# STM32F446RE_BES.net
KiCad netlist of a schematic drawn in Altium Designer
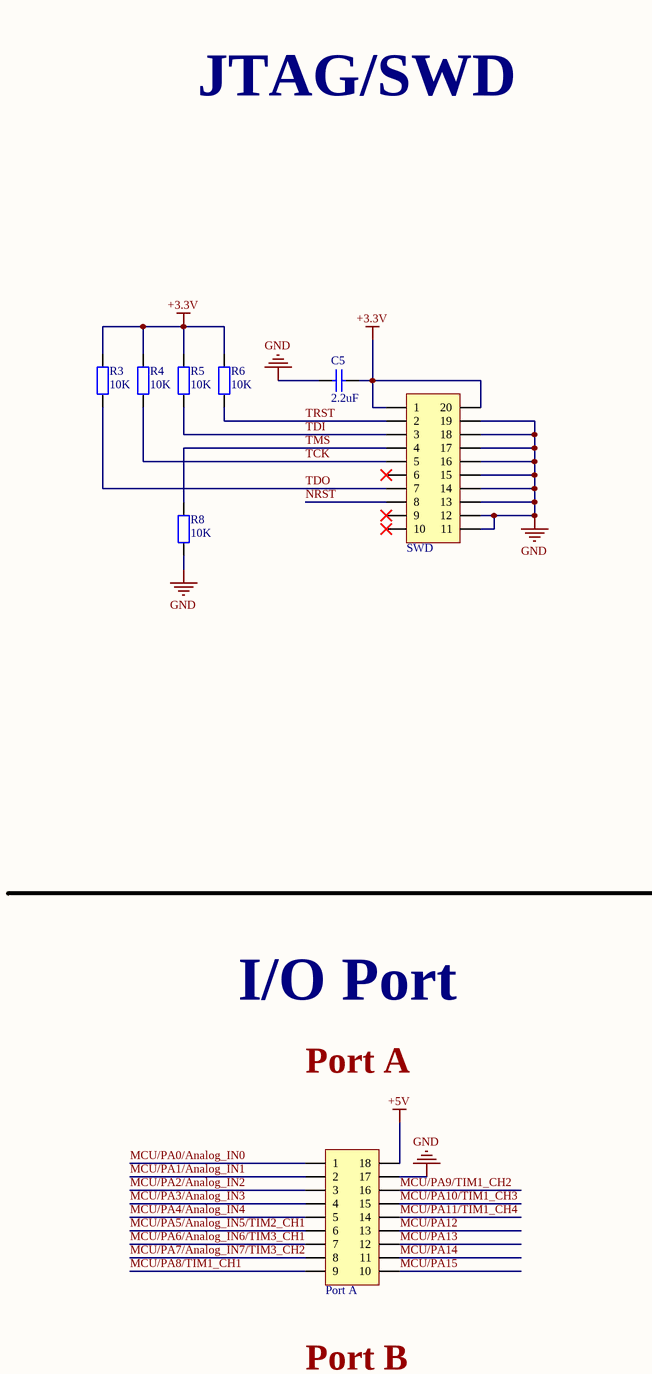
[diagram p0: STM32F446RE_BES.SchDoc, top left]
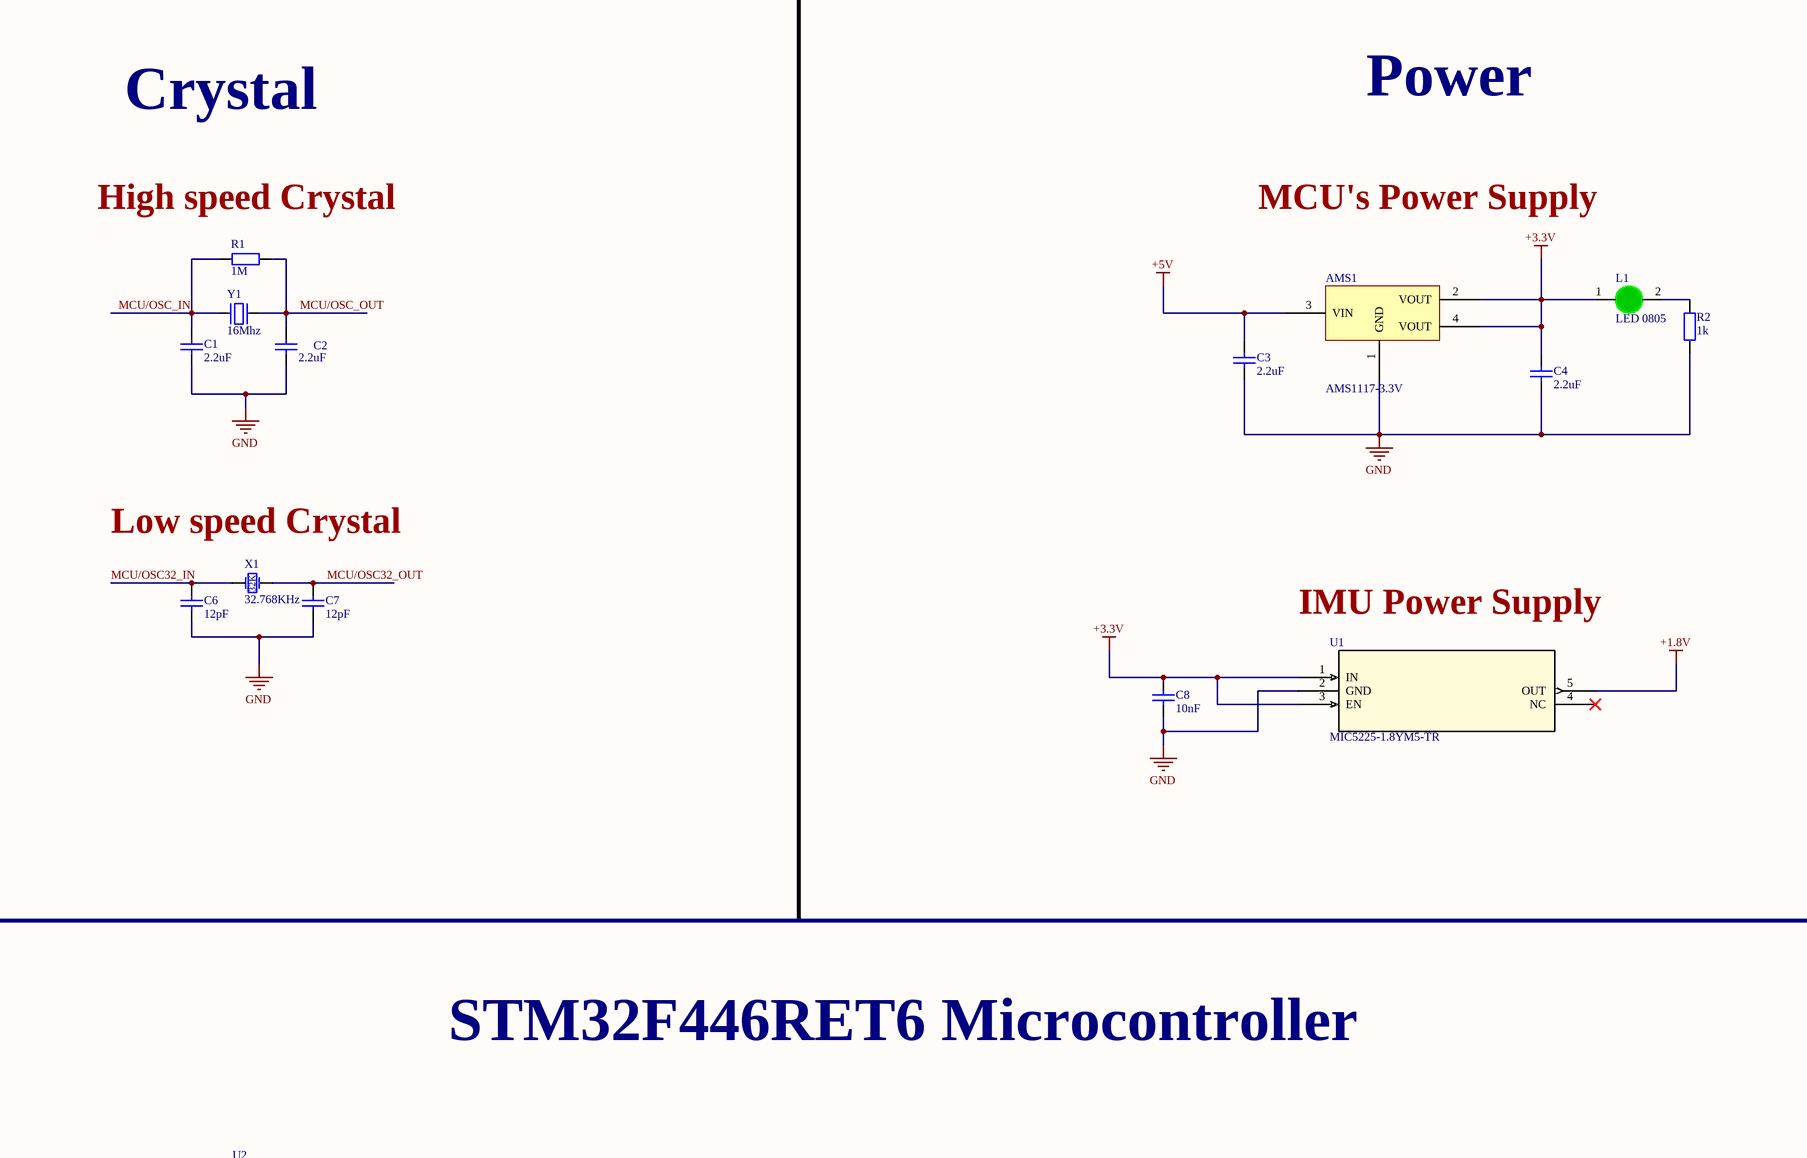
[diagram p1: STM32F446RE_BES.SchDoc, top middle]
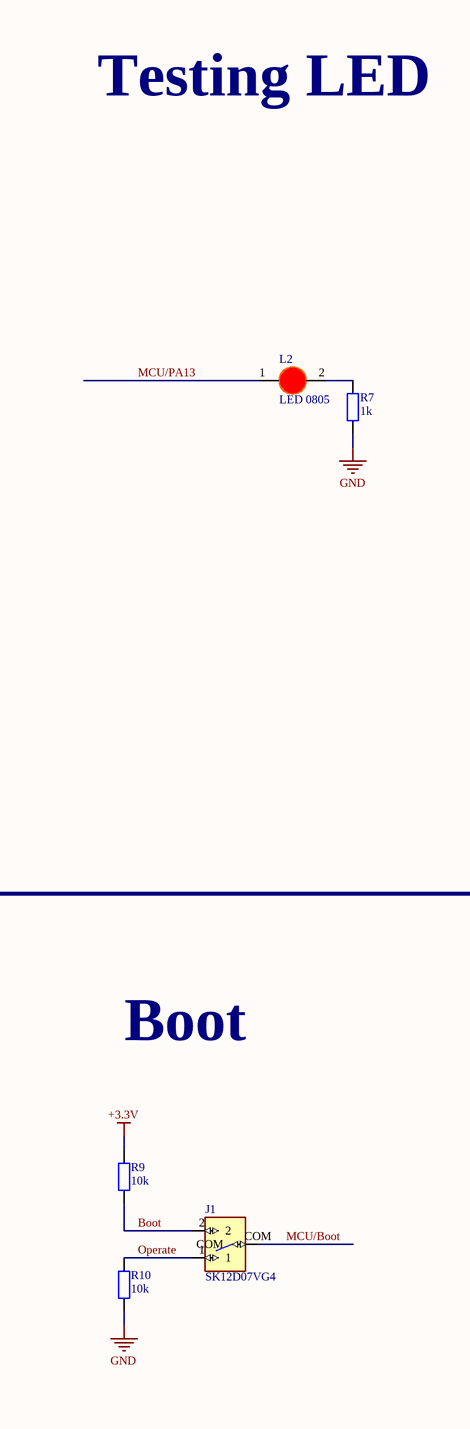
[diagram p2: STM32F446RE_BES.SchDoc, top right]
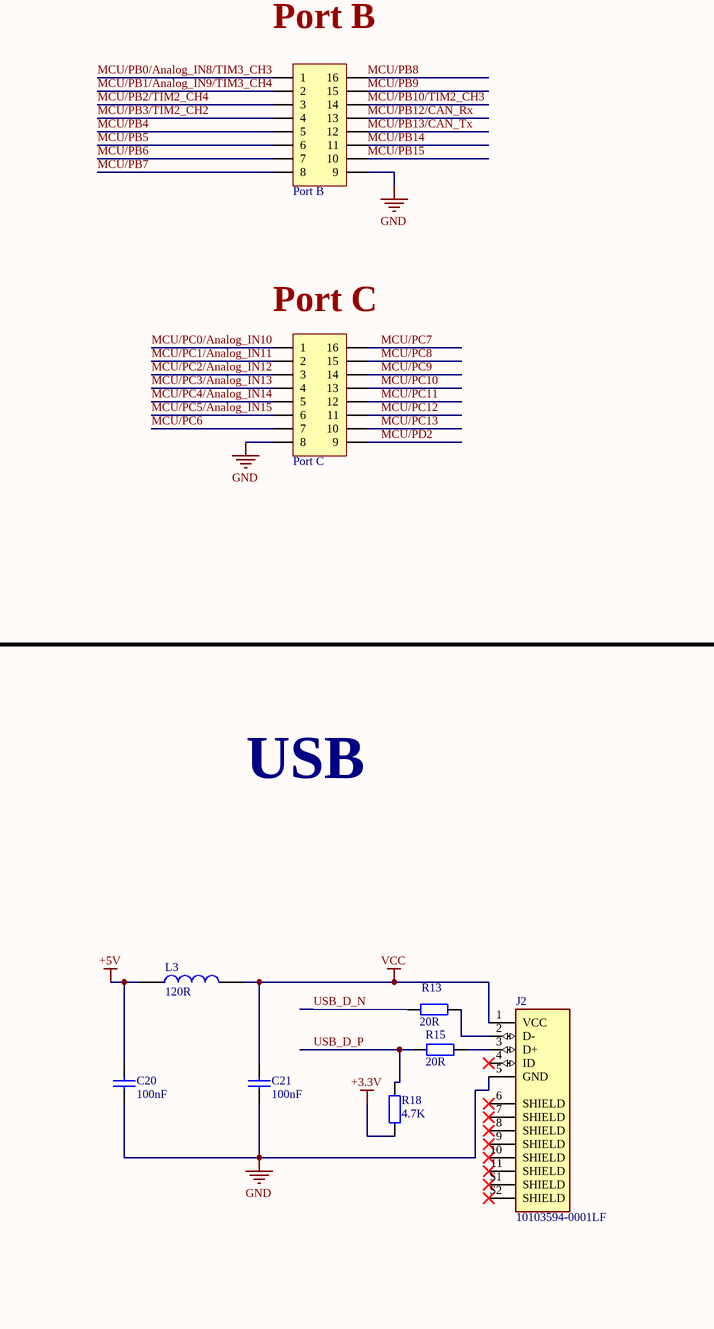
[diagram p3: STM32F446RE_BES.SchDoc, bottom left]
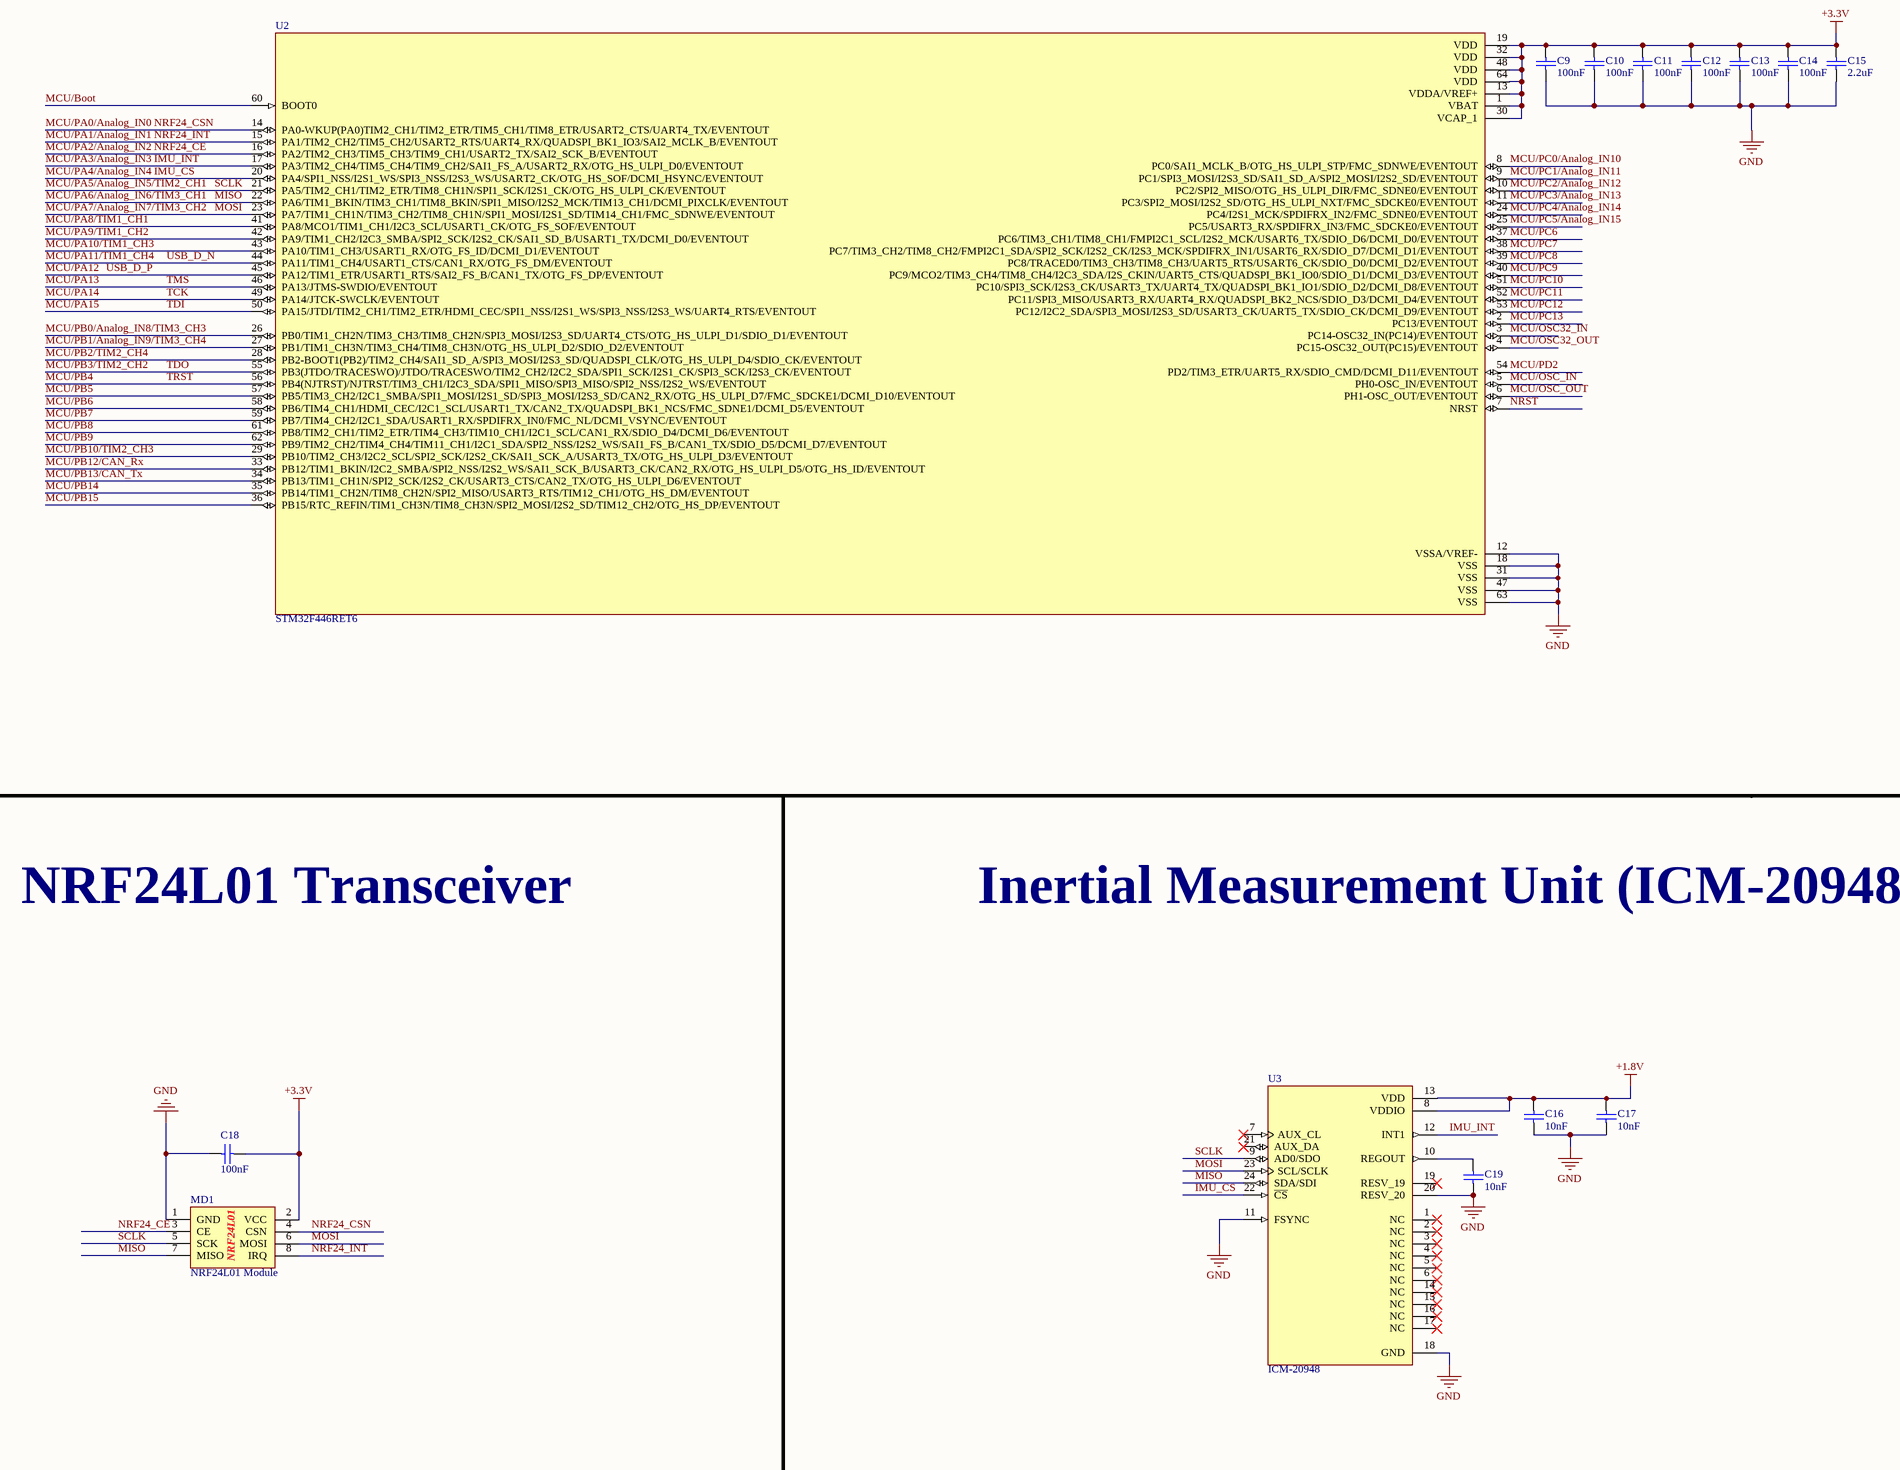
[diagram p4: STM32F446RE_BES.SchDoc, bottom middle]
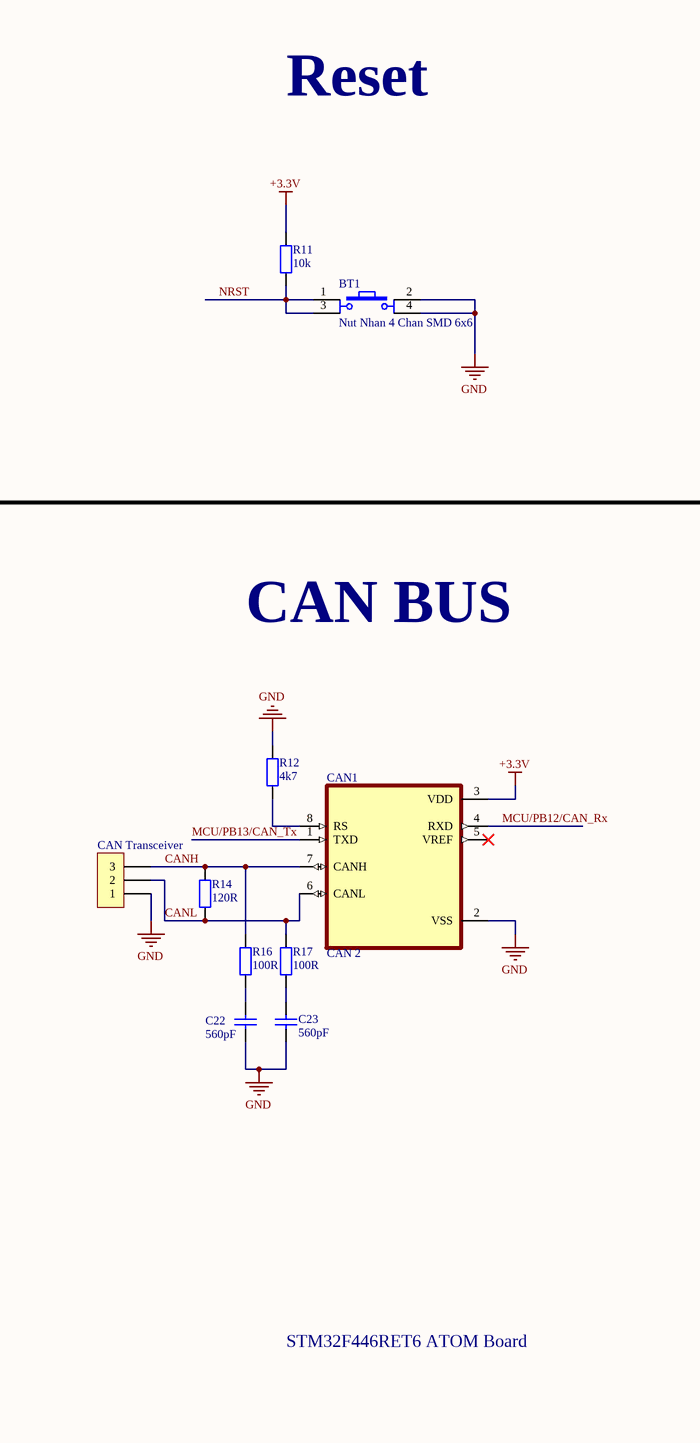
[diagram p5: STM32F446RE_BES.SchDoc, bottom right]

(export (version "E")
  (design (tool "Eeschema 10.0.6"))
  (components
    (comp (ref "AMS1")
      (value "AMS1117-3.3V")
      (footprint "SOT223")
      (description "Dán")
      (libsource (lib "Altium_Lib_by_KhueNguyenCreator") (part "AMS1117 SMD"))
    )
    (comp (ref "BT1")
      (value "Nut Nhan 4 Chan SMD 6x6")
      (footprint "Nut Nhan 4 Chan SMD 6x6")
      (description "Nut Nhan 4 Chan 6.2x6.2x3.5")
      (libsource (lib "Altium_Lib_by_KhueNguyenCreator") (part "Nut Nhan 4 Chan SMD 6x6"))
    )
    (comp (ref "C1")
      (value "2.2uF")
      (footprint "tu 0805")
      (description "Dán")
      (libsource (lib "Altium_Lib_by_KhueNguyenCreator") (part "Tu 0805 10pF 50V 10%"))
    )
    (comp (ref "C2")
      (value "2.2uF")
      (footprint "tu 0805")
      (description "Dán")
      (libsource (lib "Altium_Lib_by_KhueNguyenCreator") (part "Tu 0805 10pF 50V 10%"))
    )
    (comp (ref "C3")
      (value "2.2uF")
      (footprint "tu 0805")
      (description "Dán")
      (libsource (lib "Altium_Lib_by_KhueNguyenCreator") (part "Tu 0805 10pF 50V 10%"))
    )
    (comp (ref "C4")
      (value "2.2uF")
      (footprint "tu 0805")
      (description "Dán")
      (libsource (lib "Altium_Lib_by_KhueNguyenCreator") (part "Tu 0805 10pF 50V 10%"))
    )
    (comp (ref "C5")
      (value "2.2uF")
      (footprint "tu 0805")
      (description "Dán")
      (libsource (lib "Altium_Lib_by_KhueNguyenCreator") (part "Tu 0805 10pF 50V 10%"))
    )
    (comp (ref "C6")
      (value "12pF")
      (footprint "tu 0805")
      (description "Dán")
      (libsource (lib "Altium_Lib_by_KhueNguyenCreator") (part "Tu 0805 10pF 50V 10%"))
    )
    (comp (ref "C7")
      (value "12pF")
      (footprint "tu 0805")
      (description "Dán")
      (libsource (lib "Altium_Lib_by_KhueNguyenCreator") (part "Tu 0805 10pF 50V 10%"))
    )
    (comp (ref "C8")
      (value "10nF")
      (footprint "tu 0805")
      (description "Dán")
      (libsource (lib "Altium_Lib_by_KhueNguyenCreator") (part "Tu 0805 106 16V 10%"))
    )
    (comp (ref "C9")
      (value "100nF")
      (footprint "tu 0805")
      (description "Dán")
      (libsource (lib "Altium_Lib_by_KhueNguyenCreator") (part "Tu 0805 10pF 50V 10%"))
    )
    (comp (ref "C10")
      (value "100nF")
      (footprint "tu 0805")
      (description "Dán")
      (libsource (lib "Altium_Lib_by_KhueNguyenCreator") (part "Tu 0805 10pF 50V 10%"))
    )
    (comp (ref "C11")
      (value "100nF")
      (footprint "tu 0805")
      (description "Dán")
      (libsource (lib "Altium_Lib_by_KhueNguyenCreator") (part "Tu 0805 10pF 50V 10%"))
    )
    (comp (ref "C12")
      (value "100nF")
      (footprint "tu 0805")
      (description "Dán")
      (libsource (lib "Altium_Lib_by_KhueNguyenCreator") (part "Tu 0805 10pF 50V 10%"))
    )
    (comp (ref "C13")
      (value "100nF")
      (footprint "tu 0805")
      (description "Dán")
      (libsource (lib "Altium_Lib_by_KhueNguyenCreator") (part "Tu 0805 10pF 50V 10%"))
    )
    (comp (ref "C14")
      (value "100nF")
      (footprint "tu 0805")
      (description "Dán")
      (libsource (lib "Altium_Lib_by_KhueNguyenCreator") (part "Tu 0805 10pF 50V 10%"))
    )
    (comp (ref "C15")
      (value "2.2uF")
      (footprint "tu 0805")
      (description "Dán")
      (libsource (lib "Altium_Lib_by_KhueNguyenCreator") (part "Tu 0805 10pF 50V 10%"))
    )
    (comp (ref "C16")
      (value "10nF")
      (footprint "tu 0805")
      (description "Dán")
      (libsource (lib "Altium_Lib_by_KhueNguyenCreator") (part "Tu 0805 106 16V 10%"))
    )
    (comp (ref "C17")
      (value "10nF")
      (footprint "tu 0805")
      (description "Dán")
      (libsource (lib "Altium_Lib_by_KhueNguyenCreator") (part "Tu 0805 106 16V 10%"))
    )
    (comp (ref "C18")
      (value "100nF")
      (footprint "tu 0805")
      (description "Dán")
      (libsource (lib "Altium_Lib_by_KhueNguyenCreator") (part "Tu 0805 106 16V 10%"))
    )
    (comp (ref "C19")
      (value "10nF")
      (footprint "tu 0805")
      (description "Dán")
      (libsource (lib "Altium_Lib_by_KhueNguyenCreator") (part "Tu 0805 106 16V 10%"))
    )
    (comp (ref "C20")
      (value "100nF")
      (footprint "tu 0805")
      (description "Dán")
      (libsource (lib "Altium_Lib_by_KhueNguyenCreator") (part "Tu 0805 106 16V 10%"))
    )
    (comp (ref "C21")
      (value "100nF")
      (footprint "tu 0805")
      (description "Dán")
      (libsource (lib "Altium_Lib_by_KhueNguyenCreator") (part "Tu 0805 106 16V 10%"))
    )
    (comp (ref "C22")
      (value "560pF")
      (footprint "tu 0805")
      (description "Dán")
      (libsource (lib "Altium_Lib_by_KhueNguyenCreator") (part "Tu 0805 106 16V 10%"))
    )
    (comp (ref "C23")
      (value "560pF")
      (footprint "tu 0805")
      (description "Dán")
      (libsource (lib "Altium_Lib_by_KhueNguyenCreator") (part "Tu 0805 106 16V 10%"))
    )
    (comp (ref "CAN 1")
      (value "CAN Transceiver")
      (footprint "XH2.54M-3")
      (description "Cắm")
      (libsource (lib "Altium_Lib_by_KhueNguyenCreator") (part "Header 3P 2.54 Duc Thang"))
    )
    (comp (ref "CAN1")
      (value "CAN 2")
      (footprint "MCP2551-I_SN:SOIC127P599X175-8N")
      (fields
        (field (name "MF") "{'manufacturer': u'Microchip Technology'}")
        (field (name "MP") "MCP2551-I/SN")
      )
      (libsource (lib "*") (part "MCP2551-I/SN"))
    )
    (comp (ref "J1")
      (value "SK12D07VG4")
      (footprint "SK12D07VG4")
      (description "Switch Slide ON ON SPDT Side Slide 0.3A 30VDC PC Pins Bracket Mount/Through Hole Bulk")
      (fields (field (name "MF") "C&K"))
      (libsource (lib "SK12D07VG4") (part "SK12D07VG4"))
    )
    (comp (ref "J2")
      (value "10103594-0001LF")
      (footprint "10103594-0001LF:AMPHENOL_10103594-0001LF")
      (description "USB - micro B USB 2.0 Receptacle Connector 5 Position Surface Mount, Right Angle; Through Hole")
      (fields (field (name "MF") "{'manufacturer': u'FCI Connectors'}"))
      (libsource (lib "*") (part "10103594-0001LF"))
    )
    (comp (ref "L1")
      (value "LED 0805")
      (footprint "LED-0805-Green")
      (description "Dán")
      (libsource (lib "Altium_Lib_by_KhueNguyenCreator") (part "LED 0805 Xanh La"))
    )
    (comp (ref "L2")
      (value "LED 0805")
      (footprint "LED-0805-Red")
      (description "Dán")
      (libsource (lib "Altium_Lib_by_KhueNguyenCreator") (part "LED 0805 Do"))
    )
    (comp (ref "L3")
      (value "120R")
      (footprint "IND-0603 (1608)")
      (description "IND-FERRITE BEAD 23 OHM  4A 0603 1LN")
      (fields (field (name "MPN") "FBMJ1608HM230NT"))
      (libsource (lib "BYTECH_HW_LIB_2019 (1)") (part "FBMJ1608HM230NT"))
    )
    (comp (ref "MD1")
      (value "NRF24L01 Module")
      (footprint "NRF24L01")
      (libsource (lib "Altium_Lib_by_KhueNguyenCreator") (part "NRF24L01 Module"))
    )
    (comp (ref "Port A")
      (value "Port A")
      (footprint "JP 2x9 DT")
      (description "Cắm")
      (libsource (lib "Altium_Lib_by_KhueNguyenCreator") (part "JP 2x9 2.54 Duc Thang"))
    )
    (comp (ref "Port B")
      (value "Port B")
      (footprint "JP 2x8 DT")
      (description "Cắm")
      (libsource (lib "Altium_Lib_by_KhueNguyenCreator") (part "JP 2x8 2.54 Duc Thang"))
    )
    (comp (ref "Port C")
      (value "Port C")
      (footprint "JP 2x8 DT")
      (description "Cắm")
      (libsource (lib "Altium_Lib_by_KhueNguyenCreator") (part "JP 2x8 2.54 Duc Thang"))
    )
    (comp (ref "R1")
      (value "1M")
      (footprint "tro smd 0805")
      (description "Dán")
      (libsource (lib "Altium_Lib_by_KhueNguyenCreator") (part "Tro 0805 1% 1k"))
    )
    (comp (ref "R2")
      (value "1k")
      (footprint "tro smd 0805")
      (description "Dán")
      (libsource (lib "Altium_Lib_by_KhueNguyenCreator") (part "Tro 0805 1% 1k"))
    )
    (comp (ref "R3")
      (value "10K")
      (footprint "tro smd 0805")
      (description "Dán")
      (libsource (lib "Altium_Lib_by_KhueNguyenCreator") (part "Tro 0805 1% 10k"))
    )
    (comp (ref "R4")
      (value "10K")
      (footprint "tro smd 0805")
      (description "Dán")
      (libsource (lib "Altium_Lib_by_KhueNguyenCreator") (part "Tro 0805 1% 10k"))
    )
    (comp (ref "R5")
      (value "10K")
      (footprint "tro smd 0805")
      (description "Dán")
      (libsource (lib "Altium_Lib_by_KhueNguyenCreator") (part "Tro 0805 1% 10k"))
    )
    (comp (ref "R6")
      (value "10K")
      (footprint "tro smd 0805")
      (description "Dán")
      (libsource (lib "Altium_Lib_by_KhueNguyenCreator") (part "Tro 0805 1% 10k"))
    )
    (comp (ref "R7")
      (value "1k")
      (footprint "tro smd 0805")
      (description "Dán")
      (libsource (lib "Altium_Lib_by_KhueNguyenCreator") (part "Tro 0805 1% 1k"))
    )
    (comp (ref "R8")
      (value "10K")
      (footprint "tro smd 0805")
      (description "Dán")
      (libsource (lib "Altium_Lib_by_KhueNguyenCreator") (part "Tro 0805 1% 10k"))
    )
    (comp (ref "R9")
      (value "10k")
      (footprint "tro smd 0805")
      (description "Dán")
      (libsource (lib "Altium_Lib_by_KhueNguyenCreator") (part "Tro 0805 1% 1k"))
    )
    (comp (ref "R10")
      (value "10k")
      (footprint "tro smd 0805")
      (description "Dán")
      (libsource (lib "Altium_Lib_by_KhueNguyenCreator") (part "Tro 0805 1% 1k"))
    )
    (comp (ref "R11")
      (value "10k")
      (footprint "tro smd 0805")
      (description "Dán")
      (libsource (lib "Altium_Lib_by_KhueNguyenCreator") (part "Tro 0805 1% 1k"))
    )
    (comp (ref "R12")
      (value "4k7")
      (footprint "tro smd 0805")
      (description "Dán")
      (libsource (lib "Altium_Lib_by_KhueNguyenCreator") (part "Tro 0805 1% 10k"))
    )
    (comp (ref "R13")
      (value "20R")
      (footprint "tro smd 0805")
      (description "Dán")
      (libsource (lib "Altium_Lib_by_KhueNguyenCreator") (part "Tro 0805 1% 10k"))
    )
    (comp (ref "R14")
      (value "120R")
      (footprint "tro smd 0805")
      (description "Dán")
      (libsource (lib "Altium_Lib_by_KhueNguyenCreator") (part "Tro 0805 1% 10k"))
    )
    (comp (ref "R15")
      (value "20R")
      (footprint "tro smd 0805")
      (description "Dán")
      (libsource (lib "Altium_Lib_by_KhueNguyenCreator") (part "Tro 0805 1% 10k"))
    )
    (comp (ref "R16")
      (value "100R")
      (footprint "tro smd 0805")
      (description "Dán")
      (libsource (lib "Altium_Lib_by_KhueNguyenCreator") (part "Tro 0805 1% 10k"))
    )
    (comp (ref "R17")
      (value "100R")
      (footprint "tro smd 0805")
      (description "Dán")
      (libsource (lib "Altium_Lib_by_KhueNguyenCreator") (part "Tro 0805 1% 10k"))
    )
    (comp (ref "R18")
      (value "4.7K")
      (footprint "tro smd 0805")
      (description "Dán")
      (libsource (lib "Altium_Lib_by_KhueNguyenCreator") (part "Tro 0805 1% 10k"))
    )
    (comp (ref "SWD1")
      (value "SWD")
      (footprint "JP 2x10 DT")
      (description "Cắm")
      (libsource (lib "Altium_Lib_by_KhueNguyenCreator") (part "JP 2x10 2.54 Duc Thang"))
    )
    (comp (ref "U1")
      (value "MIC5225-1.8YM5-TR")
      (footprint "SOT-23-5_M5_MCH")
      (description "No Description Available")
      (libsource (lib "MIC5225-1P8YM5-TR") (part "MIC5225-1.8YM5-TR"))
    )
    (comp (ref "U2")
      (value "STM32F446RET6")
      (footprint "QFP50P1200X1200X160-64N")
      (description "MCU 32-Bit STM32 ARM Cortex M4 RISC 512KB Flash 2.5V/3.3V 64-Pin LQFP Tray")
      (fields (field (name "MF") "{'manufacturer': u'STMicroelectronics'}"))
      (libsource (lib "SnapEDA_Library") (part "STM32F446RET6"))
    )
    (comp (ref "U3")
      (value "ICM-20948")
      (footprint "QFN40P300X300X105-24N")
      (description "Accelerometer, Gyroscope, Magnetometer, 9 Axis Sensor IÂ²C, SPI Output")
      (libsource (lib "ICM-20948") (part "ICM-20948"))
    )
    (comp (ref "X1")
      (value "32.768KHz")
      (footprint "Crystal_ABS07_SMD-3.2x1.5MM")
      (description "CRYSTAL 32.7680KHZ 12.5pF SMD")
      (fields (field (name "MPN") "ABS07-32.768KHZ-T"))
      (libsource (lib "BYTECH_HW_LIB_2019 (1)") (part "ABS07-32.768KHZ-T"))
    )
    (comp (ref "Y1")
      (value "16Mhz")
      (footprint "Thach Anh 2 chan cam")
      (description "Crystal For all Crystal 2pin.")
      (libsource (lib "Altium_Lib_by_KhueNguyenCreator") (part "Thach Anh 2 chan Cam"))
    )
  )
  (nets
    (net (code "1") (name "+1.8V") (class "Default")
      (node (ref "C16") (pin "1") (pinfunction "1_1") (pintype "passive"))
      (node (ref "C17") (pin "1") (pinfunction "1_1") (pintype "passive"))
      (node (ref "U1") (pin "5") (pinfunction "OUT_5") (pintype "output"))
      (node (ref "U3") (pin "13") (pinfunction "VDD_13") (pintype "power_in"))
      (node (ref "U3") (pin "8") (pinfunction "VDDIO_8") (pintype "power_in"))
    )
    (net (code "2") (name "+3.3V") (class "Default")
      (node (ref "AMS1") (pin "2") (pinfunction "VOUT_2") (pintype "passive"))
      (node (ref "AMS1") (pin "4") (pinfunction "VOUT_4") (pintype "passive"))
      (node (ref "C10") (pin "1") (pinfunction "1_1") (pintype "passive"))
      (node (ref "C11") (pin "1") (pinfunction "1_1") (pintype "passive"))
      (node (ref "C12") (pin "1") (pinfunction "1_1") (pintype "passive"))
      (node (ref "C13") (pin "1") (pinfunction "1_1") (pintype "passive"))
      (node (ref "C14") (pin "1") (pinfunction "1_1") (pintype "passive"))
      (node (ref "C15") (pin "1") (pinfunction "1_1") (pintype "passive"))
      (node (ref "C18") (pin "1") (pinfunction "1_1") (pintype "passive"))
      (node (ref "C4") (pin "1") (pinfunction "1_1") (pintype "passive"))
      (node (ref "C5") (pin "2") (pinfunction "2_2") (pintype "passive"))
      (node (ref "C8") (pin "1") (pinfunction "1_1") (pintype "passive"))
      (node (ref "C9") (pin "1") (pinfunction "1_1") (pintype "passive"))
      (node (ref "CAN1") (pin "3") (pinfunction "VDD_3") (pintype "power_in"))
      (node (ref "L1") (pin "1") (pinfunction "A_1") (pintype "passive"))
      (node (ref "MD1") (pin "2") (pinfunction "VCC_2") (pintype "passive"))
      (node (ref "R11") (pin "1") (pinfunction "1_1") (pintype "passive"))
      (node (ref "R18") (pin "2") (pinfunction "2_2") (pintype "passive"))
      (node (ref "R3") (pin "2") (pinfunction "2_2") (pintype "passive"))
      (node (ref "R4") (pin "2") (pinfunction "2_2") (pintype "passive"))
      (node (ref "R5") (pin "2") (pinfunction "2_2") (pintype "passive"))
      (node (ref "R6") (pin "2") (pinfunction "2_2") (pintype "passive"))
      (node (ref "R9") (pin "1") (pinfunction "1_1") (pintype "passive"))
      (node (ref "SWD1") (pin "1") (pinfunction "1_1") (pintype "passive"))
      (node (ref "SWD1") (pin "20") (pinfunction "20_20") (pintype "passive"))
      (node (ref "U1") (pin "1") (pinfunction "IN_1") (pintype "input"))
      (node (ref "U1") (pin "3") (pinfunction "EN_3") (pintype "input"))
      (node (ref "U2") (pin "1") (pinfunction "VBAT_1") (pintype "power_in"))
      (node (ref "U2") (pin "13") (pinfunction "VDDA/VREF+_13") (pintype "power_in"))
      (node (ref "U2") (pin "19") (pinfunction "VDD_19") (pintype "power_in"))
      (node (ref "U2") (pin "30") (pinfunction "VCAP_1_30") (pintype "power_in"))
      (node (ref "U2") (pin "32") (pinfunction "VDD_32") (pintype "power_in"))
      (node (ref "U2") (pin "48") (pinfunction "VDD_48") (pintype "power_in"))
      (node (ref "U2") (pin "64") (pinfunction "VDD_64") (pintype "power_in"))
    )
    (net (code "3") (name "+5V") (class "Default")
      (node (ref "AMS1") (pin "3") (pinfunction "VIN_3") (pintype "passive"))
      (node (ref "C20") (pin "1") (pinfunction "1_1") (pintype "passive"))
      (node (ref "C3") (pin "1") (pinfunction "1_1") (pintype "passive"))
      (node (ref "L3") (pin "1") (pinfunction "1_1") (pintype "passive"))
      (node (ref "Port A") (pin "18") (pinfunction "18_18") (pintype "passive"))
    )
    (net (code "4") (name "/Boot") (class "Default")
      (node (ref "J1") (pin "2") (pinfunction "2_2") (pintype "bidirectional"))
      (node (ref "R9") (pin "2") (pinfunction "2_2") (pintype "passive"))
    )
    (net (code "5") (name "/CANH") (class "Default")
      (node (ref "CAN 1") (pin "3") (pinfunction "3_3") (pintype "passive"))
      (node (ref "CAN1") (pin "7") (pinfunction "CANH_7") (pintype "bidirectional"))
      (node (ref "R14") (pin "2") (pinfunction "2_2") (pintype "passive"))
      (node (ref "R16") (pin "2") (pinfunction "2_2") (pintype "passive"))
    )
    (net (code "6") (name "/CANL") (class "Default")
      (node (ref "CAN 1") (pin "2") (pinfunction "2_2") (pintype "passive"))
      (node (ref "CAN1") (pin "6") (pinfunction "CANL_6") (pintype "bidirectional"))
      (node (ref "R14") (pin "1") (pinfunction "1_1") (pintype "passive"))
      (node (ref "R17") (pin "2") (pinfunction "2_2") (pintype "passive"))
    )
    (net (code "7") (name "/IMU_CS") (class "Default")
      (node (ref "Port A") (pin "5") (pinfunction "5_5") (pintype "passive"))
      (node (ref "U2") (pin "20") (pinfunction "PA4/SPI1_NSS/I2S1_WS/SPI3_NSS/I2S3_WS/USART2_CK/OTG_HS_SOF/DCMI_HSYNC/EVENTOUT_20") (pintype "bidirectional"))
      (node (ref "U3") (pin "22") (pinfunction "~{CS}_22") (pintype "input"))
    )
    (net (code "8") (name "/IMU_INT") (class "Default")
      (node (ref "Port A") (pin "4") (pinfunction "4_4") (pintype "passive"))
      (node (ref "U2") (pin "17") (pinfunction "PA3/TIM2_CH4/TIM5_CH4/TIM9_CH2/SAI1_FS_A/USART2_RX/OTG_HS_ULPI_D0/EVENTOUT_17") (pintype "bidirectional"))
      (node (ref "U3") (pin "12") (pinfunction "INT1_12") (pintype "output"))
    )
    (net (code "9") (name "/MCU{slash}Boot") (class "Default")
      (node (ref "J1") (pin "COM") (pinfunction "COM_COM") (pintype "bidirectional"))
      (node (ref "U2") (pin "60") (pinfunction "BOOT0_60") (pintype "input"))
    )
    (net (code "10") (name "/MCU{slash}OSC32_IN") (class "Default")
      (node (ref "C6") (pin "1") (pinfunction "1_1") (pintype "passive"))
      (node (ref "U2") (pin "3") (pinfunction "PC14-OSC32_IN(PC14)/EVENTOUT_3") (pintype "bidirectional"))
      (node (ref "X1") (pin "1") (pinfunction "OSC1_1") (pintype "passive"))
    )
    (net (code "11") (name "/MCU{slash}OSC32_OUT") (class "Default")
      (node (ref "C7") (pin "1") (pinfunction "1_1") (pintype "passive"))
      (node (ref "U2") (pin "4") (pinfunction "PC15-OSC32_OUT(PC15)/EVENTOUT_4") (pintype "bidirectional"))
      (node (ref "X1") (pin "2") (pinfunction "OSC2_2") (pintype "passive"))
    )
    (net (code "12") (name "/MCU{slash}OSC_IN") (class "Default")
      (node (ref "C1") (pin "1") (pinfunction "1_1") (pintype "passive"))
      (node (ref "R1") (pin "1") (pinfunction "1_1") (pintype "passive"))
      (node (ref "U2") (pin "5") (pinfunction "PH0-OSC_IN/EVENTOUT_5") (pintype "bidirectional"))
      (node (ref "Y1") (pin "1") (pinfunction "1_1") (pintype "passive"))
    )
    (net (code "13") (name "/MCU{slash}OSC_OUT") (class "Default")
      (node (ref "C2") (pin "1") (pinfunction "1_1") (pintype "passive"))
      (node (ref "R1") (pin "2") (pinfunction "2_2") (pintype "passive"))
      (node (ref "U2") (pin "6") (pinfunction "PH1-OSC_OUT/EVENTOUT_6") (pintype "bidirectional"))
      (node (ref "Y1") (pin "2") (pinfunction "2_2") (pintype "passive"))
    )
    (net (code "14") (name "/MCU{slash}PA0{slash}Analog_IN0") (class "Default")
      (node (ref "MD1") (pin "4") (pinfunction "CSN_4") (pintype "passive"))
      (node (ref "Port A") (pin "1") (pinfunction "1_1") (pintype "passive"))
      (node (ref "U2") (pin "14") (pinfunction "PA0-WKUP(PA0)TIM2_CH1/TIM2_ETR/TIM5_CH1/TIM8_ETR/USART2_CTS/UART4_TX/EVENTOUT_14") (pintype "bidirectional"))
    )
    (net (code "15") (name "/MCU{slash}PA1{slash}Analog_IN1") (class "Default")
      (node (ref "MD1") (pin "8") (pinfunction "IRQ_8") (pintype "passive"))
      (node (ref "Port A") (pin "2") (pinfunction "2_2") (pintype "passive"))
      (node (ref "U2") (pin "15") (pinfunction "PA1/TIM2_CH2/TIM5_CH2/USART2_RTS/UART4_RX/QUADSPI_BK1_IO3/SAI2_MCLK_B/EVENTOUT_15") (pintype "bidirectional"))
    )
    (net (code "16") (name "/MCU{slash}PA2{slash}Analog_IN2") (class "Default")
      (node (ref "MD1") (pin "3") (pinfunction "CE_3") (pintype "passive"))
      (node (ref "Port A") (pin "3") (pinfunction "3_3") (pintype "passive"))
      (node (ref "U2") (pin "16") (pinfunction "PA2/TIM2_CH3/TIM5_CH3/TIM9_CH1/USART2_TX/SAI2_SCK_B/EVENTOUT_16") (pintype "bidirectional"))
    )
    (net (code "17") (name "/MCU{slash}PA5{slash}Analog_IN5{slash}TIM2_CH1") (class "Default")
      (node (ref "MD1") (pin "5") (pinfunction "SCK_5") (pintype "passive"))
      (node (ref "Port A") (pin "6") (pinfunction "6_6") (pintype "passive"))
      (node (ref "U2") (pin "21") (pinfunction "PA5/TIM2_CH1/TIM2_ETR/TIM8_CH1N/SPI1_SCK/I2S1_CK/OTG_HS_ULPI_CK/EVENTOUT_21") (pintype "bidirectional"))
      (node (ref "U3") (pin "9") (pinfunction "AD0/SDO_9") (pintype "bidirectional"))
    )
    (net (code "18") (name "/MCU{slash}PA6{slash}Analog_IN6{slash}TIM3_CH1") (class "Default")
      (node (ref "MD1") (pin "7") (pinfunction "MISO_7") (pintype "passive"))
      (node (ref "Port A") (pin "7") (pinfunction "7_7") (pintype "passive"))
      (node (ref "U2") (pin "22") (pinfunction "PA6/TIM1_BKIN/TIM3_CH1/TIM8_BKIN/SPI1_MISO/I2S2_MCK/TIM13_CH1/DCMI_PIXCLK/EVENTOUT_22") (pintype "bidirectional"))
      (node (ref "U3") (pin "24") (pinfunction "SDA/SDI_24") (pintype "bidirectional"))
    )
    (net (code "19") (name "/MCU{slash}PA7{slash}Analog_IN7{slash}TIM3_CH2") (class "Default")
      (node (ref "MD1") (pin "6") (pinfunction "MOSI_6") (pintype "passive"))
      (node (ref "Port A") (pin "8") (pinfunction "8_8") (pintype "passive"))
      (node (ref "U2") (pin "23") (pinfunction "PA7/TIM1_CH1N/TIM3_CH2/TIM8_CH1N/SPI1_MOSI/I2S1_SD/TIM14_CH1/FMC_SDNWE/EVENTOUT_23") (pintype "bidirectional"))
      (node (ref "U3") (pin "23") (pinfunction "SCL/SCLK_23") (pintype "input"))
    )
    (net (code "20") (name "/MCU{slash}PA8{slash}TIM1_CH1") (class "Default")
      (node (ref "Port A") (pin "9") (pinfunction "9_9") (pintype "passive"))
      (node (ref "U2") (pin "41") (pinfunction "PA8/MCO1/TIM1_CH1/I2C3_SCL/USART1_CK/OTG_FS_SOF/EVENTOUT_41") (pintype "bidirectional"))
    )
    (net (code "21") (name "/MCU{slash}PA9{slash}TIM1_CH2") (class "Default")
      (node (ref "Port A") (pin "16") (pinfunction "16_16") (pintype "passive"))
      (node (ref "U2") (pin "42") (pinfunction "PA9/TIM1_CH2/I2C3_SMBA/SPI2_SCK/I2S2_CK/SAI1_SD_B/USART1_TX/DCMI_D0/EVENTOUT_42") (pintype "bidirectional"))
    )
    (net (code "22") (name "/MCU{slash}PA10{slash}TIM1_CH3") (class "Default")
      (node (ref "Port A") (pin "15") (pinfunction "15_15") (pintype "passive"))
      (node (ref "U2") (pin "43") (pinfunction "PA10/TIM1_CH3/USART1_RX/OTG_FS_ID/DCMI_D1/EVENTOUT_43") (pintype "bidirectional"))
    )
    (net (code "23") (name "/MCU{slash}PA11{slash}TIM1_CH4") (class "Default")
      (node (ref "Port A") (pin "14") (pinfunction "14_14") (pintype "passive"))
      (node (ref "R13") (pin "2") (pinfunction "2_2") (pintype "passive"))
      (node (ref "U2") (pin "44") (pinfunction "PA11/TIM1_CH4/USART1_CTS/CAN1_RX/OTG_FS_DM/EVENTOUT_44") (pintype "bidirectional"))
    )
    (net (code "24") (name "/MCU{slash}PA12") (class "Default")
      (node (ref "Port A") (pin "13") (pinfunction "13_13") (pintype "passive"))
      (node (ref "R15") (pin "2") (pinfunction "2_2") (pintype "passive"))
      (node (ref "R18") (pin "1") (pinfunction "1_1") (pintype "passive"))
      (node (ref "U2") (pin "45") (pinfunction "PA12/TIM1_ETR/USART1_RTS/SAI2_FS_B/CAN1_TX/OTG_FS_DP/EVENTOUT_45") (pintype "bidirectional"))
    )
    (net (code "25") (name "/MCU{slash}PA13") (class "Default")
      (node (ref "L2") (pin "1") (pinfunction "A_1") (pintype "passive"))
      (node (ref "Port A") (pin "12") (pinfunction "12_12") (pintype "passive"))
      (node (ref "R8") (pin "2") (pinfunction "2_2") (pintype "passive"))
      (node (ref "SWD1") (pin "4") (pinfunction "4_4") (pintype "passive"))
      (node (ref "U2") (pin "46") (pinfunction "PA13/JTMS-SWDIO/EVENTOUT_46") (pintype "bidirectional"))
    )
    (net (code "26") (name "/MCU{slash}PA14") (class "Default")
      (node (ref "Port A") (pin "11") (pinfunction "11_11") (pintype "passive"))
      (node (ref "R4") (pin "1") (pinfunction "1_1") (pintype "passive"))
      (node (ref "SWD1") (pin "5") (pinfunction "5_5") (pintype "passive"))
      (node (ref "U2") (pin "49") (pinfunction "PA14/JTCK-SWCLK/EVENTOUT_49") (pintype "bidirectional"))
    )
    (net (code "27") (name "/MCU{slash}PA15") (class "Default")
      (node (ref "Port A") (pin "10") (pinfunction "10_10") (pintype "passive"))
      (node (ref "R5") (pin "1") (pinfunction "1_1") (pintype "passive"))
      (node (ref "SWD1") (pin "3") (pinfunction "3_3") (pintype "passive"))
      (node (ref "U2") (pin "50") (pinfunction "PA15/JTDI/TIM2_CH1/TIM2_ETR/HDMI_CEC/SPI1_NSS/I2S1_WS/SPI3_NSS/I2S3_WS/UART4_RTS/EVENTOUT_50") (pintype "bidirectional"))
    )
    (net (code "28") (name "/MCU{slash}PB0{slash}Analog_IN8{slash}TIM3_CH3") (class "Default")
      (node (ref "Port B") (pin "1") (pinfunction "1_1") (pintype "passive"))
      (node (ref "U2") (pin "26") (pinfunction "PB0/TIM1_CH2N/TIM3_CH3/TIM8_CH2N/SPI3_MOSI/I2S3_SD/UART4_CTS/OTG_HS_ULPI_D1/SDIO_D1/EVENTOUT_26") (pintype "bidirectional"))
    )
    (net (code "29") (name "/MCU{slash}PB1{slash}Analog_IN9{slash}TIM3_CH4") (class "Default")
      (node (ref "Port B") (pin "2") (pinfunction "2_2") (pintype "passive"))
      (node (ref "U2") (pin "27") (pinfunction "PB1/TIM1_CH3N/TIM3_CH4/TIM8_CH3N/OTG_HS_ULPI_D2/SDIO_D2/EVENTOUT_27") (pintype "bidirectional"))
    )
    (net (code "30") (name "/MCU{slash}PB2{slash}TIM2_CH4") (class "Default")
      (node (ref "Port B") (pin "3") (pinfunction "3_3") (pintype "passive"))
      (node (ref "U2") (pin "28") (pinfunction "PB2-BOOT1(PB2)/TIM2_CH4/SAI1_SD_A/SPI3_MOSI/I2S3_SD/QUADSPI_CLK/OTG_HS_ULPI_D4/SDIO_CK/EVENTOUT_28") (pintype "bidirectional"))
    )
    (net (code "31") (name "/MCU{slash}PB3{slash}TIM2_CH2") (class "Default")
      (node (ref "Port B") (pin "4") (pinfunction "4_4") (pintype "passive"))
      (node (ref "R3") (pin "1") (pinfunction "1_1") (pintype "passive"))
      (node (ref "SWD1") (pin "7") (pinfunction "7_7") (pintype "passive"))
      (node (ref "U2") (pin "55") (pinfunction "PB3(JTDO/TRACESWO)/JTDO/TRACESWO/TIM2_CH2/I2C2_SDA/SPI1_SCK/I2S1_CK/SPI3_SCK/I2S3_CK/EVENTOUT_55") (pintype "bidirectional"))
    )
    (net (code "32") (name "/MCU{slash}PB4") (class "Default")
      (node (ref "Port B") (pin "5") (pinfunction "5_5") (pintype "passive"))
      (node (ref "R6") (pin "1") (pinfunction "1_1") (pintype "passive"))
      (node (ref "SWD1") (pin "2") (pinfunction "2_2") (pintype "passive"))
      (node (ref "U2") (pin "56") (pinfunction "PB4(NJTRST)/NJTRST/TIM3_CH1/I2C3_SDA/SPI1_MISO/SPI3_MISO/SPI2_NSS/I2S2_WS/EVENTOUT_56") (pintype "bidirectional"))
    )
    (net (code "33") (name "/MCU{slash}PB5") (class "Default")
      (node (ref "Port B") (pin "6") (pinfunction "6_6") (pintype "passive"))
      (node (ref "U2") (pin "57") (pinfunction "PB5/TIM3_CH2/I2C1_SMBA/SPI1_MOSI/I2S1_SD/SPI3_MOSI/I2S3_SD/CAN2_RX/OTG_HS_ULPI_D7/FMC_SDCKE1/DCMI_D10/EVENTOUT_57") (pintype "bidirectional"))
    )
    (net (code "34") (name "/MCU{slash}PB6") (class "Default")
      (node (ref "Port B") (pin "7") (pinfunction "7_7") (pintype "passive"))
      (node (ref "U2") (pin "58") (pinfunction "PB6/TIM4_CH1/HDMI_CEC/I2C1_SCL/USART1_TX/CAN2_TX/QUADSPI_BK1_NCS/FMC_SDNE1/DCMI_D5/EVENTOUT_58") (pintype "bidirectional"))
    )
    (net (code "35") (name "/MCU{slash}PB7") (class "Default")
      (node (ref "Port B") (pin "8") (pinfunction "8_8") (pintype "passive"))
      (node (ref "U2") (pin "59") (pinfunction "PB7/TIM4_CH2/I2C1_SDA/USART1_RX/SPDIFRX_IN0/FMC_NL/DCMI_VSYNC/EVENTOUT_59") (pintype "bidirectional"))
    )
    (net (code "36") (name "/MCU{slash}PB8") (class "Default")
      (node (ref "Port B") (pin "16") (pinfunction "16_16") (pintype "passive"))
      (node (ref "U2") (pin "61") (pinfunction "PB8/TIM2_CH1/TIM2_ETR/TIM4_CH3/TIM10_CH1/I2C1_SCL/CAN1_RX/SDIO_D4/DCMI_D6/EVENTOUT_61") (pintype "bidirectional"))
    )
    (net (code "37") (name "/MCU{slash}PB9") (class "Default")
      (node (ref "Port B") (pin "15") (pinfunction "15_15") (pintype "passive"))
      (node (ref "U2") (pin "62") (pinfunction "PB9/TIM2_CH2/TIM4_CH4/TIM11_CH1/I2C1_SDA/SPI2_NSS/I2S2_WS/SAI1_FS_B/CAN1_TX/SDIO_D5/DCMI_D7/EVENTOUT_62") (pintype "bidirectional"))
    )
    (net (code "38") (name "/MCU{slash}PB10{slash}TIM2_CH3") (class "Default")
      (node (ref "Port B") (pin "14") (pinfunction "14_14") (pintype "passive"))
      (node (ref "U2") (pin "29") (pinfunction "PB10/TIM2_CH3/I2C2_SCL/SPI2_SCK/I2S2_CK/SAI1_SCK_A/USART3_TX/OTG_HS_ULPI_D3/EVENTOUT_29") (pintype "bidirectional"))
    )
    (net (code "39") (name "/MCU{slash}PB12{slash}CAN_Rx") (class "Default")
      (node (ref "CAN1") (pin "4") (pinfunction "RXD_4") (pintype "output"))
      (node (ref "Port B") (pin "13") (pinfunction "13_13") (pintype "passive"))
      (node (ref "U2") (pin "33") (pinfunction "PB12/TIM1_BKIN/I2C2_SMBA/SPI2_NSS/I2S2_WS/SAI1_SCK_B/USART3_CK/CAN2_RX/OTG_HS_ULPI_D5/OTG_HS_ID/EVENTOUT_33") (pintype "bidirectional"))
    )
    (net (code "40") (name "/MCU{slash}PB13{slash}CAN_Tx") (class "Default")
      (node (ref "CAN1") (pin "1") (pinfunction "TXD_1") (pintype "input"))
      (node (ref "Port B") (pin "12") (pinfunction "12_12") (pintype "passive"))
      (node (ref "U2") (pin "34") (pinfunction "PB13/TIM1_CH1N/SPI2_SCK/I2S2_CK/USART3_CTS/CAN2_TX/OTG_HS_ULPI_D6/EVENTOUT_34") (pintype "bidirectional"))
    )
    (net (code "41") (name "/MCU{slash}PB14") (class "Default")
      (node (ref "Port B") (pin "11") (pinfunction "11_11") (pintype "passive"))
      (node (ref "U2") (pin "35") (pinfunction "PB14/TIM1_CH2N/TIM8_CH2N/SPI2_MISO/USART3_RTS/TIM12_CH1/OTG_HS_DM/EVENTOUT_35") (pintype "bidirectional"))
    )
    (net (code "42") (name "/MCU{slash}PB15") (class "Default")
      (node (ref "Port B") (pin "10") (pinfunction "10_10") (pintype "passive"))
      (node (ref "U2") (pin "36") (pinfunction "PB15/RTC_REFIN/TIM1_CH3N/TIM8_CH3N/SPI2_MOSI/I2S2_SD/TIM12_CH2/OTG_HS_DP/EVENTOUT_36") (pintype "bidirectional"))
    )
    (net (code "43") (name "/MCU{slash}PC0{slash}Analog_IN10") (class "Default")
      (node (ref "Port C") (pin "1") (pinfunction "1_1") (pintype "passive"))
      (node (ref "U2") (pin "8") (pinfunction "PC0/SAI1_MCLK_B/OTG_HS_ULPI_STP/FMC_SDNWE/EVENTOUT_8") (pintype "bidirectional"))
    )
    (net (code "44") (name "/MCU{slash}PC1{slash}Analog_IN11") (class "Default")
      (node (ref "Port C") (pin "2") (pinfunction "2_2") (pintype "passive"))
      (node (ref "U2") (pin "9") (pinfunction "PC1/SPI3_MOSI/I2S3_SD/SAI1_SD_A/SPI2_MOSI/I2S2_SD/EVENTOUT_9") (pintype "bidirectional"))
    )
    (net (code "45") (name "/MCU{slash}PC2{slash}Analog_IN12") (class "Default")
      (node (ref "Port C") (pin "3") (pinfunction "3_3") (pintype "passive"))
      (node (ref "U2") (pin "10") (pinfunction "PC2/SPI2_MISO/OTG_HS_ULPI_DIR/FMC_SDNE0/EVENTOUT_10") (pintype "bidirectional"))
    )
    (net (code "46") (name "/MCU{slash}PC3{slash}Analog_IN13") (class "Default")
      (node (ref "Port C") (pin "4") (pinfunction "4_4") (pintype "passive"))
      (node (ref "U2") (pin "11") (pinfunction "PC3/SPI2_MOSI/I2S2_SD/OTG_HS_ULPI_NXT/FMC_SDCKE0/EVENTOUT_11") (pintype "bidirectional"))
    )
    (net (code "47") (name "/MCU{slash}PC4{slash}Analog_IN14") (class "Default")
      (node (ref "Port C") (pin "5") (pinfunction "5_5") (pintype "passive"))
      (node (ref "U2") (pin "24") (pinfunction "PC4/I2S1_MCK/SPDIFRX_IN2/FMC_SDNE0/EVENTOUT_24") (pintype "bidirectional"))
    )
    (net (code "48") (name "/MCU{slash}PC5{slash}Analog_IN15") (class "Default")
      (node (ref "Port C") (pin "6") (pinfunction "6_6") (pintype "passive"))
      (node (ref "U2") (pin "25") (pinfunction "PC5/USART3_RX/SPDIFRX_IN3/FMC_SDCKE0/EVENTOUT_25") (pintype "bidirectional"))
    )
    (net (code "49") (name "/MCU{slash}PC6") (class "Default")
      (node (ref "Port C") (pin "7") (pinfunction "7_7") (pintype "passive"))
      (node (ref "U2") (pin "37") (pinfunction "PC6/TIM3_CH1/TIM8_CH1/FMPI2C1_SCL/I2S2_MCK/USART6_TX/SDIO_D6/DCMI_D0/EVENTOUT_37") (pintype "bidirectional"))
    )
    (net (code "50") (name "/MCU{slash}PC7") (class "Default")
      (node (ref "Port C") (pin "16") (pinfunction "16_16") (pintype "passive"))
      (node (ref "U2") (pin "38") (pinfunction "PC7/TIM3_CH2/TIM8_CH2/FMPI2C1_SDA/SPI2_SCK/I2S2_CK/I2S3_MCK/SPDIFRX_IN1/USART6_RX/SDIO_D7/DCMI_D1/EVENTOUT_38") (pintype "bidirectional"))
    )
    (net (code "51") (name "/MCU{slash}PC8") (class "Default")
      (node (ref "Port C") (pin "15") (pinfunction "15_15") (pintype "passive"))
      (node (ref "U2") (pin "39") (pinfunction "PC8/TRACED0/TIM3_CH3/TIM8_CH3/UART5_RTS/USART6_CK/SDIO_D0/DCMI_D2/EVENTOUT_39") (pintype "bidirectional"))
    )
    (net (code "52") (name "/MCU{slash}PC9") (class "Default")
      (node (ref "Port C") (pin "14") (pinfunction "14_14") (pintype "passive"))
      (node (ref "U2") (pin "40") (pinfunction "PC9/MCO2/TIM3_CH4/TIM8_CH4/I2C3_SDA/I2S_CKIN/UART5_CTS/QUADSPI_BK1_IO0/SDIO_D1/DCMI_D3/EVENTOUT_40") (pintype "bidirectional"))
    )
    (net (code "53") (name "/MCU{slash}PC10") (class "Default")
      (node (ref "Port C") (pin "13") (pinfunction "13_13") (pintype "passive"))
      (node (ref "U2") (pin "51") (pinfunction "PC10/SPI3_SCK/I2S3_CK/USART3_TX/UART4_TX/QUADSPI_BK1_IO1/SDIO_D2/DCMI_D8/EVENTOUT_51") (pintype "bidirectional"))
    )
    (net (code "54") (name "/MCU{slash}PC11") (class "Default")
      (node (ref "Port C") (pin "12") (pinfunction "12_12") (pintype "passive"))
      (node (ref "U2") (pin "52") (pinfunction "PC11/SPI3_MISO/USART3_RX/UART4_RX/QUADSPI_BK2_NCS/SDIO_D3/DCMI_D4/EVENTOUT_52") (pintype "bidirectional"))
    )
    (net (code "55") (name "/MCU{slash}PC12") (class "Default")
      (node (ref "Port C") (pin "11") (pinfunction "11_11") (pintype "passive"))
      (node (ref "U2") (pin "53") (pinfunction "PC12/I2C2_SDA/SPI3_MOSI/I2S3_SD/USART3_CK/UART5_TX/SDIO_CK/DCMI_D9/EVENTOUT_53") (pintype "bidirectional"))
    )
    (net (code "56") (name "/MCU{slash}PC13") (class "Default")
      (node (ref "Port C") (pin "10") (pinfunction "10_10") (pintype "passive"))
      (node (ref "U2") (pin "2") (pinfunction "PC13/EVENTOUT_2") (pintype "bidirectional"))
    )
    (net (code "57") (name "/MCU{slash}PD2") (class "Default")
      (node (ref "Port C") (pin "9") (pinfunction "9_9") (pintype "passive"))
      (node (ref "U2") (pin "54") (pinfunction "PD2/TIM3_ETR/UART5_RX/SDIO_CMD/DCMI_D11/EVENTOUT_54") (pintype "bidirectional"))
    )
    (net (code "58") (name "/NRST") (class "Default")
      (node (ref "BT1") (pin "1") (pintype "passive"))
      (node (ref "BT1") (pin "3") (pintype "passive"))
      (node (ref "R11") (pin "2") (pinfunction "2_2") (pintype "passive"))
      (node (ref "SWD1") (pin "8") (pinfunction "8_8") (pintype "passive"))
      (node (ref "U2") (pin "7") (pinfunction "NRST_7") (pintype "bidirectional"))
    )
    (net (code "59") (name "/Operate") (class "Default")
      (node (ref "J1") (pin "1") (pinfunction "1_1") (pintype "bidirectional"))
      (node (ref "R10") (pin "1") (pinfunction "1_1") (pintype "passive"))
    )
    (net (code "60") (name "GND") (class "Default")
      (node (ref "AMS1") (pin "1") (pinfunction "GND_1") (pintype "passive"))
      (node (ref "BT1") (pin "2") (pintype "passive"))
      (node (ref "BT1") (pin "4") (pintype "passive"))
      (node (ref "C1") (pin "2") (pinfunction "2_2") (pintype "passive"))
      (node (ref "C10") (pin "2") (pinfunction "2_2") (pintype "passive"))
      (node (ref "C11") (pin "2") (pinfunction "2_2") (pintype "passive"))
      (node (ref "C12") (pin "2") (pinfunction "2_2") (pintype "passive"))
      (node (ref "C13") (pin "2") (pinfunction "2_2") (pintype "passive"))
      (node (ref "C14") (pin "2") (pinfunction "2_2") (pintype "passive"))
      (node (ref "C15") (pin "2") (pinfunction "2_2") (pintype "passive"))
      (node (ref "C16") (pin "2") (pinfunction "2_2") (pintype "passive"))
      (node (ref "C17") (pin "2") (pinfunction "2_2") (pintype "passive"))
      (node (ref "C18") (pin "2") (pinfunction "2_2") (pintype "passive"))
      (node (ref "C19") (pin "2") (pinfunction "2_2") (pintype "passive"))
      (node (ref "C2") (pin "2") (pinfunction "2_2") (pintype "passive"))
      (node (ref "C20") (pin "2") (pinfunction "2_2") (pintype "passive"))
      (node (ref "C21") (pin "2") (pinfunction "2_2") (pintype "passive"))
      (node (ref "C22") (pin "2") (pinfunction "2_2") (pintype "passive"))
      (node (ref "C23") (pin "2") (pinfunction "2_2") (pintype "passive"))
      (node (ref "C3") (pin "2") (pinfunction "2_2") (pintype "passive"))
      (node (ref "C4") (pin "2") (pinfunction "2_2") (pintype "passive"))
      (node (ref "C5") (pin "1") (pinfunction "1_1") (pintype "passive"))
      (node (ref "C6") (pin "2") (pinfunction "2_2") (pintype "passive"))
      (node (ref "C7") (pin "2") (pinfunction "2_2") (pintype "passive"))
      (node (ref "C8") (pin "2") (pinfunction "2_2") (pintype "passive"))
      (node (ref "C9") (pin "2") (pinfunction "2_2") (pintype "passive"))
      (node (ref "CAN 1") (pin "1") (pinfunction "1_1") (pintype "passive"))
      (node (ref "CAN1") (pin "2") (pinfunction "VSS_2") (pintype "power_in"))
      (node (ref "J2") (pin "5") (pinfunction "GND_5") (pintype "power_in"))
      (node (ref "MD1") (pin "1") (pinfunction "GND_1") (pintype "passive"))
      (node (ref "Port A") (pin "17") (pinfunction "17_17") (pintype "passive"))
      (node (ref "Port B") (pin "9") (pinfunction "9_9") (pintype "passive"))
      (node (ref "Port C") (pin "8") (pinfunction "8_8") (pintype "passive"))
      (node (ref "R10") (pin "2") (pinfunction "2_2") (pintype "passive"))
      (node (ref "R12") (pin "1") (pinfunction "1_1") (pintype "passive"))
      (node (ref "R2") (pin "2") (pinfunction "2_2") (pintype "passive"))
      (node (ref "R7") (pin "1") (pinfunction "1_1") (pintype "passive"))
      (node (ref "R8") (pin "1") (pinfunction "1_1") (pintype "passive"))
      (node (ref "SWD1") (pin "11") (pinfunction "11_11") (pintype "passive"))
      (node (ref "SWD1") (pin "12") (pinfunction "12_12") (pintype "passive"))
      (node (ref "SWD1") (pin "13") (pinfunction "13_13") (pintype "passive"))
      (node (ref "SWD1") (pin "14") (pinfunction "14_14") (pintype "passive"))
      (node (ref "SWD1") (pin "15") (pinfunction "15_15") (pintype "passive"))
      (node (ref "SWD1") (pin "16") (pinfunction "16_16") (pintype "passive"))
      (node (ref "SWD1") (pin "17") (pinfunction "17_17") (pintype "passive"))
      (node (ref "SWD1") (pin "18") (pinfunction "18_18") (pintype "passive"))
      (node (ref "SWD1") (pin "19") (pinfunction "19_19") (pintype "passive"))
      (node (ref "U1") (pin "2") (pinfunction "GND_2") (pintype "power_in"))
      (node (ref "U2") (pin "12") (pinfunction "VSSA/VREF-_12") (pintype "power_in"))
      (node (ref "U2") (pin "18") (pinfunction "VSS_18") (pintype "power_in"))
      (node (ref "U2") (pin "31") (pinfunction "VSS_31") (pintype "power_in"))
      (node (ref "U2") (pin "47") (pinfunction "VSS_47") (pintype "power_in"))
      (node (ref "U2") (pin "63") (pinfunction "VSS_63") (pintype "power_in"))
      (node (ref "U3") (pin "11") (pinfunction "FSYNC_11") (pintype "input"))
      (node (ref "U3") (pin "18") (pinfunction "GND_18") (pintype "power_in"))
      (node (ref "U3") (pin "20") (pinfunction "RESV_20_20") (pintype "passive"))
    )
    (net (code "61") (name "Net-(C22-Pad1)") (class "Default")
      (node (ref "C22") (pin "1") (pinfunction "1_1") (pintype "passive"))
      (node (ref "R16") (pin "1") (pinfunction "1_1") (pintype "passive"))
    )
    (net (code "62") (name "Net-(C23-Pad1)") (class "Default")
      (node (ref "C23") (pin "1") (pinfunction "1_1") (pintype "passive"))
      (node (ref "R17") (pin "1") (pinfunction "1_1") (pintype "passive"))
    )
    (net (code "63") (name "Net-(CAN1-RS)") (class "Default")
      (node (ref "CAN1") (pin "8") (pinfunction "RS_8") (pintype "input"))
      (node (ref "R12") (pin "2") (pinfunction "2_2") (pintype "passive"))
    )
    (net (code "64") (name "Net-(J2-D+)") (class "Default")
      (node (ref "J2") (pin "3") (pinfunction "D+_3") (pintype "bidirectional"))
      (node (ref "R15") (pin "1") (pinfunction "1_1") (pintype "passive"))
    )
    (net (code "65") (name "Net-(J2-D-)") (class "Default")
      (node (ref "J2") (pin "2") (pinfunction "D-_2") (pintype "bidirectional"))
      (node (ref "R13") (pin "1") (pinfunction "1_1") (pintype "passive"))
    )
    (net (code "66") (name "Net-(L1-K)") (class "Default")
      (node (ref "L1") (pin "2") (pinfunction "K_2") (pintype "passive"))
      (node (ref "R2") (pin "1") (pinfunction "1_1") (pintype "passive"))
    )
    (net (code "67") (name "Net-(L2-K)") (class "Default")
      (node (ref "L2") (pin "2") (pinfunction "K_2") (pintype "passive"))
      (node (ref "R7") (pin "2") (pinfunction "2_2") (pintype "passive"))
    )
    (net (code "68") (name "Net-(U3-REGOUT)") (class "Default")
      (node (ref "C19") (pin "1") (pinfunction "1_1") (pintype "passive"))
      (node (ref "U3") (pin "10") (pinfunction "REGOUT_10") (pintype "output"))
    )
    (net (code "69") (name "VCC") (class "Default")
      (node (ref "C21") (pin "1") (pinfunction "1_1") (pintype "passive"))
      (node (ref "J2") (pin "1") (pinfunction "VCC_1") (pintype "power_in"))
      (node (ref "L3") (pin "2") (pinfunction "2_2") (pintype "passive"))
    )
    (net (code "70") (name "unconnected-(CAN1-VREF-Pad5)") (class "Default")
      (node (ref "CAN1") (pin "5") (pinfunction "VREF_5") (pintype "output+no_connect"))
    )
    (net (code "71") (name "unconnected-(J2-ID-Pad4)") (class "Default")
      (node (ref "J2") (pin "4") (pinfunction "ID_4") (pintype "bidirectional+no_connect"))
    )
    (net (code "72") (name "unconnected-(J2-SHIELD-Pad6)") (class "Default")
      (node (ref "J2") (pin "6") (pinfunction "SHIELD_6") (pintype "passive+no_connect"))
    )
    (net (code "73") (name "unconnected-(J2-SHIELD-Pad7)") (class "Default")
      (node (ref "J2") (pin "7") (pinfunction "SHIELD_7") (pintype "passive+no_connect"))
    )
    (net (code "74") (name "unconnected-(J2-SHIELD-Pad8)") (class "Default")
      (node (ref "J2") (pin "8") (pinfunction "SHIELD_8") (pintype "passive+no_connect"))
    )
    (net (code "75") (name "unconnected-(J2-SHIELD-Pad9)") (class "Default")
      (node (ref "J2") (pin "9") (pinfunction "SHIELD_9") (pintype "passive+no_connect"))
    )
    (net (code "76") (name "unconnected-(J2-SHIELD-Pad10)") (class "Default")
      (node (ref "J2") (pin "10") (pinfunction "SHIELD_10") (pintype "passive+no_connect"))
    )
    (net (code "77") (name "unconnected-(J2-SHIELD-Pad11)") (class "Default")
      (node (ref "J2") (pin "11") (pinfunction "SHIELD_11") (pintype "passive+no_connect"))
    )
    (net (code "78") (name "unconnected-(J2-SHIELD-PadS1)") (class "Default")
      (node (ref "J2") (pin "S1") (pinfunction "SHIELD_S1") (pintype "passive+no_connect"))
    )
    (net (code "79") (name "unconnected-(J2-SHIELD-PadS2)") (class "Default")
      (node (ref "J2") (pin "S2") (pinfunction "SHIELD_S2") (pintype "passive+no_connect"))
    )
    (net (code "80") (name "unconnected-(SWD1-Pad6)") (class "Default")
      (node (ref "SWD1") (pin "6") (pinfunction "6_6") (pintype "passive+no_connect"))
    )
    (net (code "81") (name "unconnected-(SWD1-Pad9)") (class "Default")
      (node (ref "SWD1") (pin "9") (pinfunction "9_9") (pintype "passive+no_connect"))
    )
    (net (code "82") (name "unconnected-(SWD1-Pad10)") (class "Default")
      (node (ref "SWD1") (pin "10") (pinfunction "10_10") (pintype "passive+no_connect"))
    )
    (net (code "83") (name "unconnected-(U1-NC-Pad4)") (class "Default")
      (node (ref "U1") (pin "4") (pinfunction "NC_4") (pintype "passive+no_connect"))
    )
    (net (code "84") (name "unconnected-(U3-AUX_CL-Pad7)") (class "Default")
      (node (ref "U3") (pin "7") (pinfunction "AUX_CL_7") (pintype "input+no_connect"))
    )
    (net (code "85") (name "unconnected-(U3-AUX_DA-Pad21)") (class "Default")
      (node (ref "U3") (pin "21") (pinfunction "AUX_DA_21") (pintype "bidirectional+no_connect"))
    )
    (net (code "86") (name "unconnected-(U3-NC-Pad1)") (class "Default")
      (node (ref "U3") (pin "1") (pinfunction "NC_1") (pintype "passive+no_connect"))
    )
    (net (code "87") (name "unconnected-(U3-NC-Pad2)") (class "Default")
      (node (ref "U3") (pin "2") (pinfunction "NC_2") (pintype "passive+no_connect"))
    )
    (net (code "88") (name "unconnected-(U3-NC-Pad3)") (class "Default")
      (node (ref "U3") (pin "3") (pinfunction "NC_3") (pintype "passive+no_connect"))
    )
    (net (code "89") (name "unconnected-(U3-NC-Pad4)") (class "Default")
      (node (ref "U3") (pin "4") (pinfunction "NC_4") (pintype "passive+no_connect"))
    )
    (net (code "90") (name "unconnected-(U3-NC-Pad5)") (class "Default")
      (node (ref "U3") (pin "5") (pinfunction "NC_5") (pintype "passive+no_connect"))
    )
    (net (code "91") (name "unconnected-(U3-NC-Pad6)") (class "Default")
      (node (ref "U3") (pin "6") (pinfunction "NC_6") (pintype "passive+no_connect"))
    )
    (net (code "92") (name "unconnected-(U3-NC-Pad14)") (class "Default")
      (node (ref "U3") (pin "14") (pinfunction "NC_14") (pintype "passive+no_connect"))
    )
    (net (code "93") (name "unconnected-(U3-NC-Pad15)") (class "Default")
      (node (ref "U3") (pin "15") (pinfunction "NC_15") (pintype "passive+no_connect"))
    )
    (net (code "94") (name "unconnected-(U3-NC-Pad16)") (class "Default")
      (node (ref "U3") (pin "16") (pinfunction "NC_16") (pintype "passive+no_connect"))
    )
    (net (code "95") (name "unconnected-(U3-NC-Pad17)") (class "Default")
      (node (ref "U3") (pin "17") (pinfunction "NC_17") (pintype "passive+no_connect"))
    )
    (net (code "96") (name "unconnected-(U3-RESV_19-Pad19)") (class "Default")
      (node (ref "U3") (pin "19") (pinfunction "RESV_19_19") (pintype "passive+no_connect"))
    )
  )
)
